# Phase_Modulator_Transmitter.net
KiCad netlist of a schematic drawn in Altium Designer
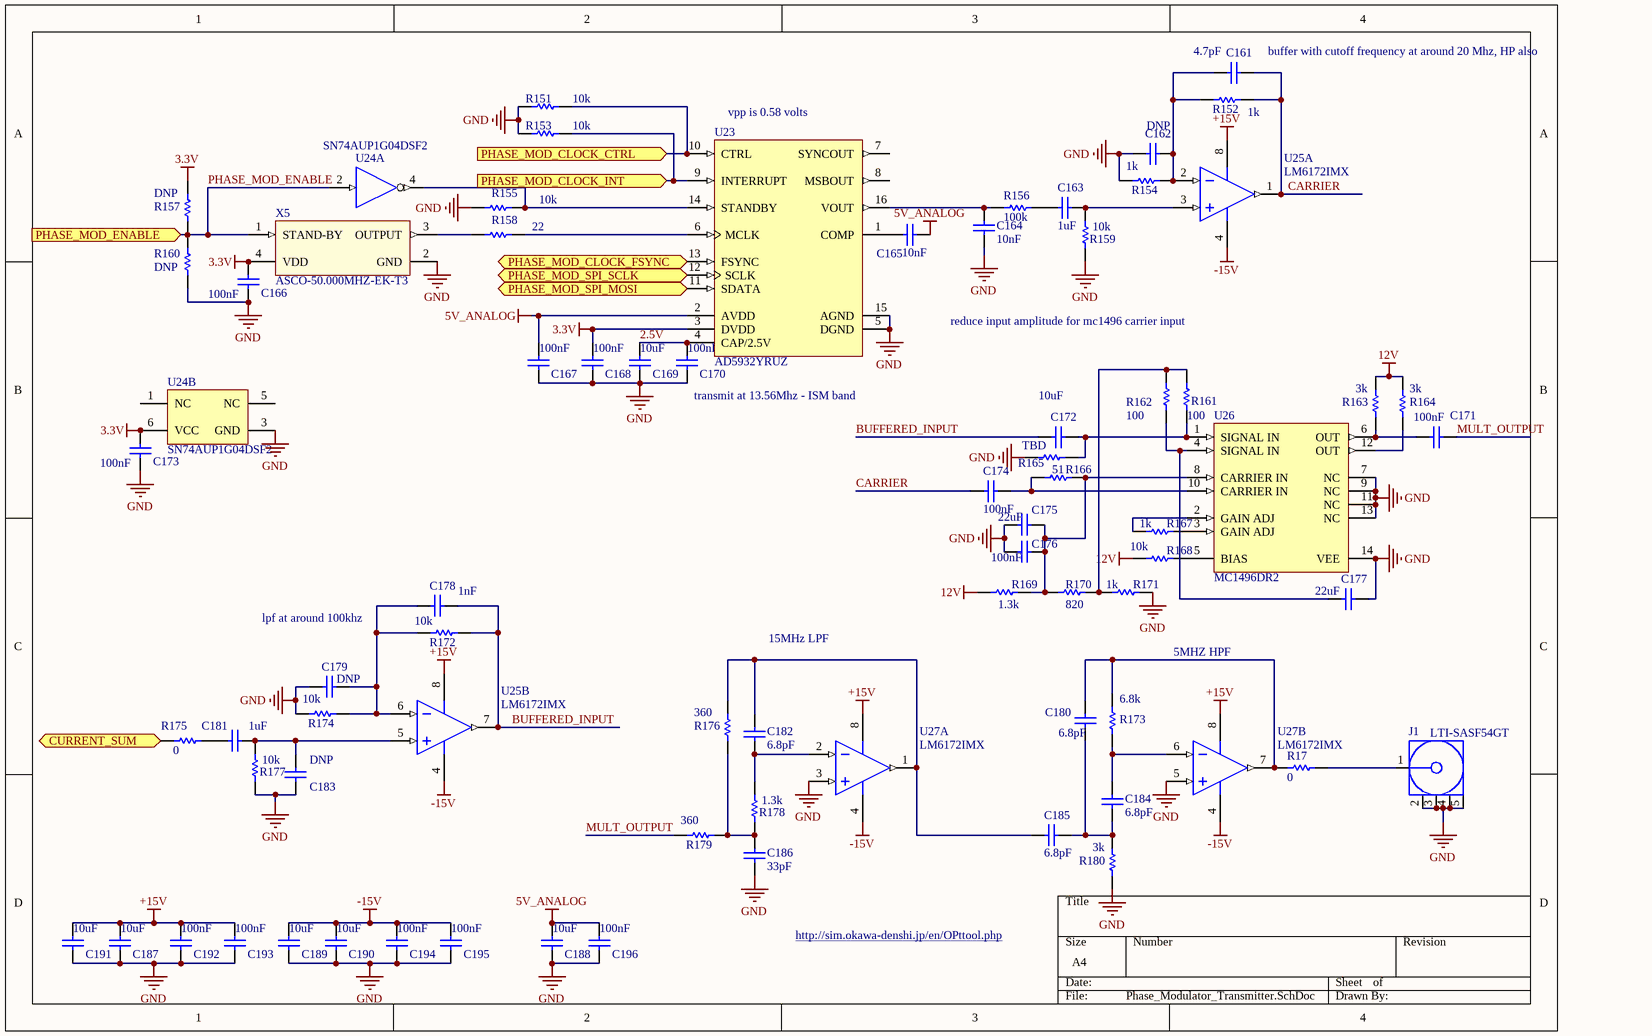
[diagram p0: Phase_Modulator_Transmitter.SchDoc]

(export (version "E")
  (design (tool "Eeschema 10.0.6"))
  (components
    (comp (ref "C161")
      (value "4.7pF")
      (footprint "CAPC0402(1005)60_L")
      (description "0402 (1005 Metric) Chip Capacitor")
      (fields (field (name "Comment") "CAP0402"))
      (libsource (lib "Altium Content Vault") (part "CMP-1590-00004-1"))
    )
    (comp (ref "C162")
      (value "DNP")
      (footprint "CAPC0402(1005)60_L")
      (description "0402 (1005 Metric) Chip Capacitor")
      (fields (field (name "Comment") "CAP0402"))
      (libsource (lib "Altium Content Vault") (part "CMP-1590-00004-1"))
    )
    (comp (ref "C163")
      (value "1uF")
      (footprint "CAPC0402(1005)60_L")
      (description "0402 (1005 Metric) Chip Capacitor")
      (fields (field (name "Comment") "CAP0402"))
      (libsource (lib "Altium Content Vault") (part "CMP-1590-00004-1"))
    )
    (comp (ref "C164")
      (value "10nF")
      (footprint "CAPC0402(1005)60_L")
      (description "0402 (1005 Metric) Chip Capacitor")
      (fields (field (name "Comment") "CAP0402"))
      (libsource (lib "Altium Content Vault") (part "CMP-1590-00004-1"))
    )
    (comp (ref "C165")
      (value "10nF")
      (footprint "CAPC0402(1005)60_L")
      (description "0402 (1005 Metric) Chip Capacitor")
      (fields (field (name "Comment") "CAP0402"))
      (libsource (lib "Altium Content Vault") (part "CMP-1590-00004-1"))
    )
    (comp (ref "C166")
      (value "100nF")
      (footprint "CAPC0402(1005)60_L")
      (description "0402 (1005 Metric) Chip Capacitor")
      (fields (field (name "Comment") "CAP0402"))
      (libsource (lib "Altium Content Vault") (part "CMP-1590-00004-1"))
    )
    (comp (ref "C167")
      (value "100nF")
      (footprint "CAPC0402(1005)60_L")
      (description "0402 (1005 Metric) Chip Capacitor")
      (fields (field (name "Comment") "CAP0402"))
      (libsource (lib "Altium Content Vault") (part "CMP-1590-00004-1"))
    )
    (comp (ref "C168")
      (value "100nF")
      (footprint "CAPC0402(1005)60_L")
      (description "0402 (1005 Metric) Chip Capacitor")
      (fields (field (name "Comment") "CAP0402"))
      (libsource (lib "Altium Content Vault") (part "CMP-1590-00004-1"))
    )
    (comp (ref "C169")
      (value "10uF")
      (footprint "CAPC0402(1005)60_L")
      (description "0402 (1005 Metric) Chip Capacitor")
      (fields (field (name "Comment") "CAP0402"))
      (libsource (lib "Altium Content Vault") (part "CMP-1590-00004-1"))
    )
    (comp (ref "C170")
      (value "100nF")
      (footprint "CAPC0402(1005)60_L")
      (description "0402 (1005 Metric) Chip Capacitor")
      (fields (field (name "Comment") "CAP0402"))
      (libsource (lib "Altium Content Vault") (part "CMP-1590-00004-1"))
    )
    (comp (ref "C171")
      (value "CAP0402")
      (footprint "CAPC0402(1005)60_L")
      (description "0402 (1005 Metric) Chip Capacitor")
      (fields (field (name "TOLERANCE") "100nF"))
      (libsource (lib "Altium Content Vault") (part "CMP-1590-00004-1"))
    )
    (comp (ref "C172")
      (value "10uF")
      (footprint "CAPC0805(2012)145_L")
      (description "0805 (2012 Metric) Chip Capacitor")
      (fields (field (name "Comment") "CAP0805"))
      (libsource (lib "Altium Content Vault") (part "CMP-1590-00003-1"))
    )
    (comp (ref "C173")
      (value "100nF")
      (footprint "CAPC0402(1005)60_L")
      (description "0402 (1005 Metric) Chip Capacitor")
      (fields (field (name "Comment") "CAP0402"))
      (libsource (lib "Altium Content Vault") (part "CMP-1590-00004-1"))
    )
    (comp (ref "C174")
      (value "100nF")
      (footprint "CAPC0402(1005)60_L")
      (description "0402 (1005 Metric) Chip Capacitor")
      (fields (field (name "Comment") "CAP0402"))
      (libsource (lib "Altium Content Vault") (part "CMP-1590-00004-1"))
    )
    (comp (ref "C175")
      (value "22uF")
      (footprint "CAPC0805(2012)145_L")
      (description "0805 (2012 Metric) Chip Capacitor")
      (fields (field (name "Comment") "CAP0805"))
      (libsource (lib "Altium Content Vault") (part "CMP-1590-00003-1"))
    )
    (comp (ref "C176")
      (value "100nF")
      (footprint "CAPC0402(1005)60_L")
      (description "0402 (1005 Metric) Chip Capacitor")
      (fields (field (name "Comment") "CAP0402"))
      (libsource (lib "Altium Content Vault") (part "CMP-1590-00004-1"))
    )
    (comp (ref "C177")
      (value "22uF")
      (footprint "CAPC0805(2012)145_L")
      (description "0805 (2012 Metric) Chip Capacitor")
      (fields (field (name "Comment") "CAP0805"))
      (libsource (lib "Altium Content Vault") (part "CMP-1590-00003-1"))
    )
    (comp (ref "C178")
      (value "1nF")
      (footprint "CAPC0402(1005)60_L")
      (description "0402 (1005 Metric) Chip Capacitor")
      (fields (field (name "Comment") "CAP0402"))
      (libsource (lib "Altium Content Vault") (part "CMP-1590-00004-1"))
    )
    (comp (ref "C179")
      (value "DNP")
      (footprint "CAPC0402(1005)60_L")
      (description "0402 (1005 Metric) Chip Capacitor")
      (fields (field (name "Comment") "CAP0402"))
      (libsource (lib "Altium Content Vault") (part "CMP-1590-00004-1"))
    )
    (comp (ref "C180")
      (value "6.8pF")
      (footprint "CAPC0402(1005)60_L")
      (description "0402 (1005 Metric) Chip Capacitor")
      (fields (field (name "Comment") "CAP0402"))
      (libsource (lib "Altium Content Vault") (part "CMP-1590-00004-1"))
    )
    (comp (ref "C181")
      (value "1uF")
      (footprint "CAPC0402(1005)60_L")
      (description "0402 (1005 Metric) Chip Capacitor")
      (fields (field (name "Comment") "CAP0402"))
      (libsource (lib "Altium Content Vault") (part "CMP-1590-00004-1"))
    )
    (comp (ref "C182")
      (value "6.8pF")
      (footprint "CAPC0402(1005)60_L")
      (description "0402 (1005 Metric) Chip Capacitor")
      (fields (field (name "Comment") "CAP0402"))
      (libsource (lib "Altium Content Vault") (part "CMP-1590-00004-1"))
    )
    (comp (ref "C183")
      (value "DNP")
      (footprint "CAPC0402(1005)60_L")
      (description "0402 (1005 Metric) Chip Capacitor")
      (fields (field (name "Comment") "CAP0402"))
      (libsource (lib "Altium Content Vault") (part "CMP-1590-00004-1"))
    )
    (comp (ref "C184")
      (value "6.8pF")
      (footprint "CAPC0402(1005)60_L")
      (description "0402 (1005 Metric) Chip Capacitor")
      (fields (field (name "Comment") "CAP0402"))
      (libsource (lib "Altium Content Vault") (part "CMP-1590-00004-1"))
    )
    (comp (ref "C185")
      (value "6.8pF")
      (footprint "CAPC0402(1005)60_L")
      (description "0402 (1005 Metric) Chip Capacitor")
      (fields (field (name "Comment") "CAP0402"))
      (libsource (lib "Altium Content Vault") (part "CMP-1590-00004-1"))
    )
    (comp (ref "C186")
      (value "33pF")
      (footprint "CAPC0402(1005)60_L")
      (description "0402 (1005 Metric) Chip Capacitor")
      (fields (field (name "Comment") "CAP0402"))
      (libsource (lib "Altium Content Vault") (part "CMP-1590-00004-1"))
    )
    (comp (ref "C187")
      (value "10uF")
      (footprint "CAPC0805(2012)145_L")
      (description "0805 (2012 Metric) Chip Capacitor")
      (fields (field (name "Comment") "CAP0805"))
      (libsource (lib "Altium Content Vault") (part "CMP-1590-00003-1"))
    )
    (comp (ref "C188")
      (value "10uF")
      (footprint "CAPC0805(2012)145_L")
      (description "0805 (2012 Metric) Chip Capacitor")
      (fields (field (name "Comment") "CAP0805"))
      (libsource (lib "Altium Content Vault") (part "CMP-1590-00003-1"))
    )
    (comp (ref "C189")
      (value "10uF")
      (footprint "CAPC0805(2012)145_L")
      (description "0805 (2012 Metric) Chip Capacitor")
      (fields (field (name "Comment") "CAP0805"))
      (libsource (lib "Altium Content Vault") (part "CMP-1590-00003-1"))
    )
    (comp (ref "C190")
      (value "10uF")
      (footprint "CAPC0805(2012)145_L")
      (description "0805 (2012 Metric) Chip Capacitor")
      (fields (field (name "Comment") "CAP0805"))
      (libsource (lib "Altium Content Vault") (part "CMP-1590-00003-1"))
    )
    (comp (ref "C191")
      (value "10uF")
      (footprint "CAPC0805(2012)145_L")
      (description "0805 (2012 Metric) Chip Capacitor")
      (fields (field (name "Comment") "CAP0805"))
      (libsource (lib "Altium Content Vault") (part "CMP-1590-00003-1"))
    )
    (comp (ref "C192")
      (value "100nF")
      (footprint "CAPC0402(1005)60_L")
      (description "0402 (1005 Metric) Chip Capacitor")
      (fields (field (name "Comment") "CAP0402"))
      (libsource (lib "Altium Content Vault") (part "CMP-1590-00004-1"))
    )
    (comp (ref "C193")
      (value "100nF")
      (footprint "CAPC0402(1005)60_L")
      (description "0402 (1005 Metric) Chip Capacitor")
      (fields (field (name "Comment") "CAP0402"))
      (libsource (lib "Altium Content Vault") (part "CMP-1590-00004-1"))
    )
    (comp (ref "C194")
      (value "100nF")
      (footprint "CAPC0402(1005)60_L")
      (description "0402 (1005 Metric) Chip Capacitor")
      (fields (field (name "Comment") "CAP0402"))
      (libsource (lib "Altium Content Vault") (part "CMP-1590-00004-1"))
    )
    (comp (ref "C195")
      (value "100nF")
      (footprint "CAPC0402(1005)60_L")
      (description "0402 (1005 Metric) Chip Capacitor")
      (fields (field (name "Comment") "CAP0402"))
      (libsource (lib "Altium Content Vault") (part "CMP-1590-00004-1"))
    )
    (comp (ref "C196")
      (value "100nF")
      (footprint "CAPC0402(1005)60_L")
      (description "0402 (1005 Metric) Chip Capacitor")
      (fields (field (name "Comment") "CAP0402"))
      (libsource (lib "Altium Content Vault") (part "CMP-1590-00004-1"))
    )
    (comp (ref "J1")
      (value "LTI-SASF54GT")
      (footprint "LHT-LTI-SASF54GT_V")
      (description "SMA Connector, Pitch 2.54 mm, 1 Position, Height 9.5 mm, Tail Length 4 mm, RoHS")
      (fields (field (name "MANUFACTURER") "Lighthorse Technologies Inc."))
      (libsource (lib "Altium Content Vault") (part "CN-S-F-RF5"))
    )
    (comp (ref "R17")
      (value "0")
      (footprint "RESC0402(1005)_L")
      (description "0402 (1005 Metric) Chip Resistor")
      (fields (field (name "Comment") "RES0402"))
      (libsource (lib "Altium Content Vault") (part "CMP-1591-00004-1"))
    )
    (comp (ref "R151")
      (value "10k")
      (footprint "RESC0402(1005)_L")
      (description "0402 (1005 Metric) Chip Resistor")
      (fields (field (name "Comment") "RES0402"))
      (libsource (lib "Altium Content Vault") (part "CMP-1591-00004-1"))
    )
    (comp (ref "R152")
      (value "1k")
      (footprint "RESC0402(1005)_L")
      (description "0402 (1005 Metric) Chip Resistor")
      (fields (field (name "Comment") "RES0402"))
      (libsource (lib "Altium Content Vault") (part "CMP-1591-00004-1"))
    )
    (comp (ref "R153")
      (value "10k")
      (footprint "RESC0402(1005)_L")
      (description "0402 (1005 Metric) Chip Resistor")
      (fields (field (name "Comment") "RES0402"))
      (libsource (lib "Altium Content Vault") (part "CMP-1591-00004-1"))
    )
    (comp (ref "R154")
      (value "1k")
      (footprint "RESC0402(1005)_L")
      (description "0402 (1005 Metric) Chip Resistor")
      (fields (field (name "Comment") "RES0402"))
      (libsource (lib "Altium Content Vault") (part "CMP-1591-00004-1"))
    )
    (comp (ref "R155")
      (value "10k")
      (footprint "RESC0402(1005)_L")
      (description "0402 (1005 Metric) Chip Resistor")
      (fields (field (name "Comment") "RES0402"))
      (libsource (lib "Altium Content Vault") (part "CMP-1591-00004-1"))
    )
    (comp (ref "R156")
      (value "100k")
      (footprint "RESC0402(1005)_L")
      (description "0402 (1005 Metric) Chip Resistor")
      (fields (field (name "Comment") "RES0402"))
      (libsource (lib "Altium Content Vault") (part "CMP-1591-00004-1"))
    )
    (comp (ref "R157")
      (value "DNP")
      (footprint "RESC0402(1005)_L")
      (description "0402 (1005 Metric) Chip Resistor")
      (fields (field (name "Comment") "RES0402"))
      (libsource (lib "Altium Content Vault") (part "CMP-1591-00004-1"))
    )
    (comp (ref "R158")
      (value "22")
      (footprint "RESC0402(1005)_L")
      (description "0402 (1005 Metric) Chip Resistor")
      (fields (field (name "Comment") "RES0402"))
      (libsource (lib "Altium Content Vault") (part "CMP-1591-00004-1"))
    )
    (comp (ref "R159")
      (value "10k")
      (footprint "RESC0402(1005)_L")
      (description "0402 (1005 Metric) Chip Resistor")
      (fields (field (name "Comment") "RES0402"))
      (libsource (lib "Altium Content Vault") (part "CMP-1591-00004-1"))
    )
    (comp (ref "R160")
      (value "DNP")
      (footprint "RESC0402(1005)_L")
      (description "0402 (1005 Metric) Chip Resistor")
      (fields (field (name "Comment") "RES0402"))
      (libsource (lib "Altium Content Vault") (part "CMP-1591-00004-1"))
    )
    (comp (ref "R161")
      (value "100")
      (footprint "RESC0402(1005)_L")
      (description "0402 (1005 Metric) Chip Resistor")
      (fields (field (name "Comment") "RES0402"))
      (libsource (lib "Altium Content Vault") (part "CMP-1591-00004-1"))
    )
    (comp (ref "R162")
      (value "100")
      (footprint "RESC0402(1005)_L")
      (description "0402 (1005 Metric) Chip Resistor")
      (fields (field (name "Comment") "RES0402"))
      (libsource (lib "Altium Content Vault") (part "CMP-1591-00004-1"))
    )
    (comp (ref "R163")
      (value "3k")
      (footprint "RESC0402(1005)_L")
      (description "0402 (1005 Metric) Chip Resistor")
      (fields (field (name "Comment") "RES0402"))
      (libsource (lib "Altium Content Vault") (part "CMP-1591-00004-1"))
    )
    (comp (ref "R164")
      (value "3k")
      (footprint "RESC0402(1005)_L")
      (description "0402 (1005 Metric) Chip Resistor")
      (fields (field (name "Comment") "RES0402"))
      (libsource (lib "Altium Content Vault") (part "CMP-1591-00004-1"))
    )
    (comp (ref "R165")
      (value "TBD")
      (footprint "RESC0402(1005)_L")
      (description "0402 (1005 Metric) Chip Resistor")
      (fields (field (name "Comment") "RES0402"))
      (libsource (lib "Altium Content Vault") (part "CMP-1591-00004-1"))
    )
    (comp (ref "R166")
      (value "51")
      (footprint "RESC0402(1005)_L")
      (description "0402 (1005 Metric) Chip Resistor")
      (fields (field (name "Comment") "RES0402"))
      (libsource (lib "Altium Content Vault") (part "CMP-1591-00004-1"))
    )
    (comp (ref "R167")
      (value "1k")
      (footprint "RESC0402(1005)_L")
      (description "0402 (1005 Metric) Chip Resistor")
      (fields (field (name "Comment") "RES0402"))
      (libsource (lib "Altium Content Vault") (part "CMP-1591-00004-1"))
    )
    (comp (ref "R168")
      (value "10k")
      (footprint "RESC0402(1005)_L")
      (description "0402 (1005 Metric) Chip Resistor")
      (fields (field (name "Comment") "RES0402"))
      (libsource (lib "Altium Content Vault") (part "CMP-1591-00004-1"))
    )
    (comp (ref "R169")
      (value "1.3k")
      (footprint "RESC0402(1005)_L")
      (description "0402 (1005 Metric) Chip Resistor")
      (fields (field (name "Comment") "RES0402"))
      (libsource (lib "Altium Content Vault") (part "CMP-1591-00004-1"))
    )
    (comp (ref "R170")
      (value "820")
      (footprint "RESC0402(1005)_L")
      (description "0402 (1005 Metric) Chip Resistor")
      (fields (field (name "Comment") "RES0402"))
      (libsource (lib "Altium Content Vault") (part "CMP-1591-00004-1"))
    )
    (comp (ref "R171")
      (value "1k")
      (footprint "RESC0402(1005)_L")
      (description "0402 (1005 Metric) Chip Resistor")
      (fields (field (name "Comment") "RES0402"))
      (libsource (lib "Altium Content Vault") (part "CMP-1591-00004-1"))
    )
    (comp (ref "R172")
      (value "10k")
      (footprint "RESC0402(1005)_L")
      (description "0402 (1005 Metric) Chip Resistor")
      (fields (field (name "Comment") "RES0402"))
      (libsource (lib "Altium Content Vault") (part "CMP-1591-00004-1"))
    )
    (comp (ref "R173")
      (value "6.8k")
      (footprint "RESC0402(1005)_L")
      (description "0402 (1005 Metric) Chip Resistor")
      (fields (field (name "Comment") "RES0402"))
      (libsource (lib "Altium Content Vault") (part "CMP-1591-00004-1"))
    )
    (comp (ref "R174")
      (value "10k")
      (footprint "RESC0402(1005)_L")
      (description "0402 (1005 Metric) Chip Resistor")
      (fields (field (name "Comment") "RES0402"))
      (libsource (lib "Altium Content Vault") (part "CMP-1591-00004-1"))
    )
    (comp (ref "R175")
      (value "0")
      (footprint "RESC0402(1005)_L")
      (description "0402 (1005 Metric) Chip Resistor")
      (fields (field (name "Comment") "RES0402"))
      (libsource (lib "Altium Content Vault") (part "CMP-1591-00004-1"))
    )
    (comp (ref "R176")
      (value "360")
      (footprint "RESC0402(1005)_L")
      (description "0402 (1005 Metric) Chip Resistor")
      (fields (field (name "Comment") "RES0402"))
      (libsource (lib "Altium Content Vault") (part "CMP-1591-00004-1"))
    )
    (comp (ref "R177")
      (value "10k")
      (footprint "RESC0402(1005)_L")
      (description "0402 (1005 Metric) Chip Resistor")
      (fields (field (name "Comment") "RES0402"))
      (libsource (lib "Altium Content Vault") (part "CMP-1591-00004-1"))
    )
    (comp (ref "R178")
      (value "1.3k")
      (footprint "RESC0402(1005)_L")
      (description "0402 (1005 Metric) Chip Resistor")
      (fields (field (name "Comment") "RES0402"))
      (libsource (lib "Altium Content Vault") (part "CMP-1591-00004-1"))
    )
    (comp (ref "R179")
      (value "360")
      (footprint "RESC0402(1005)_L")
      (description "0402 (1005 Metric) Chip Resistor")
      (fields (field (name "Comment") "RES0402"))
      (libsource (lib "Altium Content Vault") (part "CMP-1591-00004-1"))
    )
    (comp (ref "R180")
      (value "3k")
      (footprint "RESC0402(1005)_L")
      (description "0402 (1005 Metric) Chip Resistor")
      (fields (field (name "Comment") "RES0402"))
      (libsource (lib "Altium Content Vault") (part "CMP-1591-00004-1"))
    )
    (comp (ref "U23")
      (value "AD5932YRUZ")
      (footprint "ADI-RU-16_M")
      (description "Programmable Frequency Scan Waveform Generator, 10-Bit, Serial, RU-16, 96 Tube, Pb-Free")
      (libsource (lib "Altium Content Vault") (part "ADI-AD5932-RU-16"))
    )
    (comp (ref "U24")
      (value "SN74AUP1G04DSF2")
      (footprint "DSF0006A_V")
      (description "Low-Power Single Inverter Gate, DSF0006A, LARGE T&R")
      (fields
        (field (name "MANUFACTURER") "Texas Instruments")
        (field (name "GENERIC PART NUMBER") "SN74AUP1G04")
      )
      (libsource (lib "Altium Content Vault") (part "TI-SN74XXX1GX4-6"))
    )
    (comp (ref "U25")
      (value "LM6172IMX")
      (footprint "D0008A_L")
      (description "Dual High Speed, Low Power, Low Distortion Voltage Feedback Amplifiers, 8-pin Narrow SOIC")
      (fields (field (name "MANUFACTURER") "Texas Instruments"))
      (libsource (lib "Altium Content Vault") (part "AMP-OPA-LM6132-8"))
    )
    (comp (ref "U26")
      (value "MC1496DR2")
      (footprint "ONSC-SOIC-14-751A-03_H_V")
      (description "Balanced Modulator / Demodulator, 0 to 70 degC, 14-Pin SOIC, Tape and Reel")
      (fields (field (name "MANUFACTURER") "On Semiconductor"))
      (libsource (lib "Altium Content Vault") (part "ONSC-MC1496_B-14"))
    )
    (comp (ref "U27")
      (value "LM6172IMX")
      (footprint "D0008A_L")
      (description "Dual High Speed, Low Power, Low Distortion Voltage Feedback Amplifiers, 8-pin Narrow SOIC")
      (fields (field (name "MANUFACTURER") "Texas Instruments"))
      (libsource (lib "Altium Content Vault") (part "AMP-OPA-LM6132-8"))
    )
    (comp (ref "X5")
      (value "ASCO-50.000MHZ-EK-T3")
      (footprint "ABRA-ASCO-50.000MHZ-EK-T3-4_V")
      (description "Crystal Clock Oscillator, 50 MHz, -20 to 70 degC, 1.6 x 1.2 x 0.7 mm SMD")
      (fields (field (name "MANUFACTURER") "Abracon"))
      (libsource (lib "Altium Content Vault") (part "ABRA-ASCO-50_000MHZ-EK-T3-4"))
    )
  )
  (nets
    (net (code "1") (name "+15V") (class "Default")
      (node (ref "C187") (pin "2") (pinfunction "2_2") (pintype "passive"))
      (node (ref "C191") (pin "2") (pinfunction "2_2") (pintype "passive"))
      (node (ref "C192") (pin "1") (pinfunction "1_1") (pintype "passive"))
      (node (ref "C193") (pin "1") (pinfunction "1_1") (pintype "passive"))
      (node (ref "U25") (pin "8") (pinfunction "V+_8") (pintype "power_in"))
      (node (ref "U27") (pin "8") (pinfunction "V+_8") (pintype "power_in"))
    )
    (net (code "2") (name "-15V") (class "Default")
      (node (ref "C189") (pin "2") (pinfunction "2_2") (pintype "passive"))
      (node (ref "C190") (pin "2") (pinfunction "2_2") (pintype "passive"))
      (node (ref "C194") (pin "1") (pinfunction "1_1") (pintype "passive"))
      (node (ref "C195") (pin "1") (pinfunction "1_1") (pintype "passive"))
      (node (ref "U25") (pin "4") (pinfunction "V-_4") (pintype "power_in"))
      (node (ref "U27") (pin "4") (pinfunction "V-_4") (pintype "power_in"))
    )
    (net (code "3") (name "/2.5V") (class "Default")
      (node (ref "C169") (pin "1") (pinfunction "1_1") (pintype "passive"))
      (node (ref "C170") (pin "1") (pinfunction "1_1") (pintype "passive"))
      (node (ref "U23") (pin "4") (pinfunction "CAP/2.5V_4") (pintype "power_in"))
    )
    (net (code "4") (name "/BUFFERED_INPUT") (class "Default")
      (node (ref "C172") (pin "1") (pinfunction "1_1") (pintype "passive"))
      (node (ref "C178") (pin "2") (pinfunction "2_2") (pintype "passive"))
      (node (ref "R172") (pin "2") (pinfunction "2_2") (pintype "passive"))
      (node (ref "U25") (pin "7") (pinfunction "OUTB_7") (pintype "output"))
    )
    (net (code "5") (name "/CARRIER") (class "Default")
      (node (ref "C161") (pin "2") (pinfunction "2_2") (pintype "passive"))
      (node (ref "C174") (pin "1") (pinfunction "1_1") (pintype "passive"))
      (node (ref "R152") (pin "2") (pinfunction "2_2") (pintype "passive"))
      (node (ref "U25") (pin "1") (pinfunction "OUTA_1") (pintype "output"))
    )
    (net (code "6") (name "/CURRENT_SUM") (class "Default")
      (node (ref "R175") (pin "1") (pinfunction "1_1") (pintype "passive"))
    )
    (net (code "7") (name "/MULT_OUTPUT") (class "Default")
      (node (ref "C171") (pin "2") (pinfunction "2_2") (pintype "passive"))
      (node (ref "R179") (pin "1") (pinfunction "1_1") (pintype "passive"))
    )
    (net (code "8") (name "/PHASE_MOD_CLOCK_CTRL") (class "Default")
      (node (ref "R151") (pin "1") (pinfunction "1_1") (pintype "passive"))
      (node (ref "U23") (pin "10") (pinfunction "CTRL_10") (pintype "input"))
    )
    (net (code "9") (name "/PHASE_MOD_CLOCK_FSYNC") (class "Default")
      (node (ref "U23") (pin "13") (pinfunction "FSYNC_13") (pintype "input"))
    )
    (net (code "10") (name "/PHASE_MOD_CLOCK_INT") (class "Default")
      (node (ref "R153") (pin "1") (pinfunction "1_1") (pintype "passive"))
      (node (ref "U23") (pin "9") (pinfunction "INTERRUPT_9") (pintype "input"))
    )
    (net (code "11") (name "/PHASE_MOD_ENABLE") (class "Default")
      (node (ref "R157") (pin "1") (pinfunction "1_1") (pintype "passive"))
      (node (ref "R160") (pin "2") (pinfunction "2_2") (pintype "passive"))
      (node (ref "U24") (pin "2") (pinfunction "A_2") (pintype "input"))
      (node (ref "X5") (pin "1") (pinfunction "STAND-BY_1") (pintype "input"))
    )
    (net (code "12") (name "/PHASE_MOD_SPI_MOSI") (class "Default")
      (node (ref "U23") (pin "11") (pinfunction "SDATA_11") (pintype "input"))
    )
    (net (code "13") (name "/PHASE_MOD_SPI_SCLK") (class "Default")
      (node (ref "U23") (pin "12") (pinfunction "SCLK_12") (pintype "input"))
    )
    (net (code "14") (name "3.3V") (class "Default")
      (node (ref "C166") (pin "1") (pinfunction "1_1") (pintype "passive"))
      (node (ref "C168") (pin "1") (pinfunction "1_1") (pintype "passive"))
      (node (ref "C173") (pin "1") (pinfunction "1_1") (pintype "passive"))
      (node (ref "R157") (pin "2") (pinfunction "2_2") (pintype "passive"))
      (node (ref "U23") (pin "3") (pinfunction "DVDD_3") (pintype "power_in"))
      (node (ref "U24") (pin "6") (pinfunction "VCC_6") (pintype "power_in"))
      (node (ref "X5") (pin "4") (pinfunction "VDD_4") (pintype "power_in"))
    )
    (net (code "15") (name "5V_ANALOG") (class "Default")
      (node (ref "C165") (pin "2") (pinfunction "2_2") (pintype "passive"))
      (node (ref "C167") (pin "1") (pinfunction "1_1") (pintype "passive"))
      (node (ref "C188") (pin "2") (pinfunction "2_2") (pintype "passive"))
      (node (ref "C196") (pin "1") (pinfunction "1_1") (pintype "passive"))
      (node (ref "U23") (pin "2") (pinfunction "AVDD_2") (pintype "power_in"))
    )
    (net (code "16") (name "12V") (class "Default")
      (node (ref "R163") (pin "1") (pinfunction "1_1") (pintype "passive"))
      (node (ref "R164") (pin "1") (pinfunction "1_1") (pintype "passive"))
      (node (ref "R168") (pin "2") (pinfunction "2_2") (pintype "passive"))
      (node (ref "R169") (pin "2") (pinfunction "2_2") (pintype "passive"))
    )
    (net (code "17") (name "GND") (class "Default")
      (node (ref "C162") (pin "1") (pinfunction "1_1") (pintype "passive"))
      (node (ref "C164") (pin "1") (pinfunction "1_1") (pintype "passive"))
      (node (ref "C166") (pin "2") (pinfunction "2_2") (pintype "passive"))
      (node (ref "C167") (pin "2") (pinfunction "2_2") (pintype "passive"))
      (node (ref "C168") (pin "2") (pinfunction "2_2") (pintype "passive"))
      (node (ref "C169") (pin "2") (pinfunction "2_2") (pintype "passive"))
      (node (ref "C170") (pin "2") (pinfunction "2_2") (pintype "passive"))
      (node (ref "C173") (pin "2") (pinfunction "2_2") (pintype "passive"))
      (node (ref "C175") (pin "1") (pinfunction "1_1") (pintype "passive"))
      (node (ref "C176") (pin "1") (pinfunction "1_1") (pintype "passive"))
      (node (ref "C177") (pin "2") (pinfunction "2_2") (pintype "passive"))
      (node (ref "C179") (pin "1") (pinfunction "1_1") (pintype "passive"))
      (node (ref "C183") (pin "2") (pinfunction "2_2") (pintype "passive"))
      (node (ref "C186") (pin "2") (pinfunction "2_2") (pintype "passive"))
      (node (ref "C187") (pin "1") (pinfunction "1_1") (pintype "passive"))
      (node (ref "C188") (pin "1") (pinfunction "1_1") (pintype "passive"))
      (node (ref "C189") (pin "1") (pinfunction "1_1") (pintype "passive"))
      (node (ref "C190") (pin "1") (pinfunction "1_1") (pintype "passive"))
      (node (ref "C191") (pin "1") (pinfunction "1_1") (pintype "passive"))
      (node (ref "C192") (pin "2") (pinfunction "2_2") (pintype "passive"))
      (node (ref "C193") (pin "2") (pinfunction "2_2") (pintype "passive"))
      (node (ref "C194") (pin "2") (pinfunction "2_2") (pintype "passive"))
      (node (ref "C195") (pin "2") (pinfunction "2_2") (pintype "passive"))
      (node (ref "C196") (pin "2") (pinfunction "2_2") (pintype "passive"))
      (node (ref "J1") (pin "2") (pinfunction "2_2") (pintype "passive"))
      (node (ref "J1") (pin "3") (pinfunction "3_3") (pintype "passive"))
      (node (ref "J1") (pin "4") (pinfunction "4_4") (pintype "passive"))
      (node (ref "J1") (pin "5") (pinfunction "5_5") (pintype "passive"))
      (node (ref "R151") (pin "2") (pinfunction "2_2") (pintype "passive"))
      (node (ref "R153") (pin "2") (pinfunction "2_2") (pintype "passive"))
      (node (ref "R154") (pin "1") (pinfunction "1_1") (pintype "passive"))
      (node (ref "R155") (pin "2") (pinfunction "2_2") (pintype "passive"))
      (node (ref "R159") (pin "1") (pinfunction "1_1") (pintype "passive"))
      (node (ref "R160") (pin "1") (pinfunction "1_1") (pintype "passive"))
      (node (ref "R165") (pin "1") (pinfunction "1_1") (pintype "passive"))
      (node (ref "R171") (pin "1") (pinfunction "1_1") (pintype "passive"))
      (node (ref "R174") (pin "1") (pinfunction "1_1") (pintype "passive"))
      (node (ref "R177") (pin "2") (pinfunction "2_2") (pintype "passive"))
      (node (ref "R180") (pin "2") (pinfunction "2_2") (pintype "passive"))
      (node (ref "U23") (pin "15") (pinfunction "AGND_15") (pintype "power_in"))
      (node (ref "U23") (pin "5") (pinfunction "DGND_5") (pintype "power_in"))
      (node (ref "U24") (pin "3") (pinfunction "GND_3") (pintype "power_in"))
      (node (ref "U26") (pin "11") (pinfunction "NC_11") (pintype "passive"))
      (node (ref "U26") (pin "13") (pinfunction "NC_13") (pintype "passive"))
      (node (ref "U26") (pin "14") (pinfunction "VEE_14") (pintype "power_in"))
      (node (ref "U26") (pin "7") (pinfunction "NC_7") (pintype "passive"))
      (node (ref "U26") (pin "9") (pinfunction "NC_9") (pintype "passive"))
      (node (ref "U27") (pin "3") (pinfunction "INA+_3") (pintype "input"))
      (node (ref "U27") (pin "5") (pinfunction "INB+_5") (pintype "input"))
      (node (ref "X5") (pin "2") (pinfunction "GND_2") (pintype "power_in"))
    )
    (net (code "18") (name "Net-(C163-Pad2)") (class "Default")
      (node (ref "C163") (pin "2") (pinfunction "2_2") (pintype "passive"))
      (node (ref "R156") (pin "1") (pinfunction "1_1") (pintype "passive"))
    )
    (net (code "19") (name "Net-(C171-Pad1)") (class "Default")
      (node (ref "C171") (pin "1") (pinfunction "1_1") (pintype "passive"))
      (node (ref "R163") (pin "2") (pinfunction "2_2") (pintype "passive"))
      (node (ref "U26") (pin "6") (pinfunction "OUT_6") (pintype "output"))
    )
    (net (code "20") (name "Net-(C172-Pad2)") (class "Default")
      (node (ref "C172") (pin "2") (pinfunction "2_2") (pintype "passive"))
      (node (ref "R161") (pin "2") (pinfunction "2_2") (pintype "passive"))
      (node (ref "R165") (pin "2") (pinfunction "2_2") (pintype "passive"))
      (node (ref "U26") (pin "1") (pinfunction "SIGNAL_IN_1") (pintype "input"))
    )
    (net (code "21") (name "Net-(C174-Pad2)") (class "Default")
      (node (ref "C174") (pin "2") (pinfunction "2_2") (pintype "passive"))
      (node (ref "R166") (pin "2") (pinfunction "2_2") (pintype "passive"))
      (node (ref "U26") (pin "10") (pinfunction "CARRIER_IN_10") (pintype "input"))
    )
    (net (code "22") (name "Net-(C175-Pad2)") (class "Default")
      (node (ref "C175") (pin "2") (pinfunction "2_2") (pintype "passive"))
      (node (ref "C176") (pin "2") (pinfunction "2_2") (pintype "passive"))
      (node (ref "R166") (pin "1") (pinfunction "1_1") (pintype "passive"))
      (node (ref "R169") (pin "1") (pinfunction "1_1") (pintype "passive"))
      (node (ref "R170") (pin "2") (pinfunction "2_2") (pintype "passive"))
      (node (ref "U26") (pin "8") (pinfunction "CARRIER_IN_8") (pintype "input"))
    )
    (net (code "23") (name "Net-(C177-Pad1)") (class "Default")
      (node (ref "C177") (pin "1") (pinfunction "1_1") (pintype "passive"))
      (node (ref "R162") (pin "2") (pinfunction "2_2") (pintype "passive"))
      (node (ref "U26") (pin "4") (pinfunction "SIGNAL_IN_4") (pintype "input"))
    )
    (net (code "24") (name "Net-(C180-Pad1)") (class "Default")
      (node (ref "C180") (pin "1") (pinfunction "1_1") (pintype "passive"))
      (node (ref "C184") (pin "1") (pinfunction "1_1") (pintype "passive"))
      (node (ref "C185") (pin "1") (pinfunction "1_1") (pintype "passive"))
      (node (ref "R180") (pin "1") (pinfunction "1_1") (pintype "passive"))
    )
    (net (code "25") (name "Net-(C181-Pad1)") (class "Default")
      (node (ref "C181") (pin "1") (pinfunction "1_1") (pintype "passive"))
      (node (ref "R175") (pin "2") (pinfunction "2_2") (pintype "passive"))
    )
    (net (code "26") (name "Net-(C186-Pad1)") (class "Default")
      (node (ref "C186") (pin "1") (pinfunction "1_1") (pintype "passive"))
      (node (ref "R176") (pin "1") (pinfunction "1_1") (pintype "passive"))
      (node (ref "R178") (pin "1") (pinfunction "1_1") (pintype "passive"))
      (node (ref "R179") (pin "2") (pinfunction "2_2") (pintype "passive"))
    )
    (net (code "27") (name "Net-(J1-Pad1)") (class "Default")
      (node (ref "J1") (pin "1") (pinfunction "1_1") (pintype "passive"))
      (node (ref "R17") (pin "2") (pinfunction "2_2") (pintype "passive"))
    )
    (net (code "28") (name "Net-(R161-Pad1)") (class "Default")
      (node (ref "R161") (pin "1") (pinfunction "1_1") (pintype "passive"))
      (node (ref "R162") (pin "1") (pinfunction "1_1") (pintype "passive"))
      (node (ref "R170") (pin "1") (pinfunction "1_1") (pintype "passive"))
      (node (ref "R171") (pin "2") (pinfunction "2_2") (pintype "passive"))
    )
    (net (code "29") (name "Net-(R164-Pad2)") (class "Default")
      (node (ref "R164") (pin "2") (pinfunction "2_2") (pintype "passive"))
      (node (ref "U26") (pin "12") (pinfunction "OUT_12") (pintype "output"))
    )
    (net (code "30") (name "Net-(R167-Pad1)") (class "Default")
      (node (ref "R167") (pin "1") (pinfunction "1_1") (pintype "passive"))
      (node (ref "U26") (pin "3") (pinfunction "GAIN_ADJ_3") (pintype "input"))
    )
    (net (code "31") (name "Net-(R167-Pad2)") (class "Default")
      (node (ref "R167") (pin "2") (pinfunction "2_2") (pintype "passive"))
      (node (ref "U26") (pin "2") (pinfunction "GAIN_ADJ_2") (pintype "input"))
    )
    (net (code "32") (name "Net-(U23-COMP)") (class "Default")
      (node (ref "C165") (pin "1") (pinfunction "1_1") (pintype "passive"))
      (node (ref "U23") (pin "1") (pinfunction "COMP_1") (pintype "passive"))
    )
    (net (code "33") (name "Net-(U23-MCLK)") (class "Default")
      (node (ref "R158") (pin "1") (pinfunction "1_1") (pintype "passive"))
      (node (ref "U23") (pin "6") (pinfunction "MCLK_6") (pintype "input"))
    )
    (net (code "34") (name "Net-(U23-STANDBY)") (class "Default")
      (node (ref "R155") (pin "1") (pinfunction "1_1") (pintype "passive"))
      (node (ref "U23") (pin "14") (pinfunction "STANDBY_14") (pintype "input"))
      (node (ref "U24") (pin "4") (pinfunction "Y_4") (pintype "output"))
    )
    (net (code "35") (name "Net-(U23-VOUT)") (class "Default")
      (node (ref "C164") (pin "2") (pinfunction "2_2") (pintype "passive"))
      (node (ref "R156") (pin "2") (pinfunction "2_2") (pintype "passive"))
      (node (ref "U23") (pin "16") (pinfunction "VOUT_16") (pintype "output"))
    )
    (net (code "36") (name "Net-(U25A-INA+)") (class "Default")
      (node (ref "C163") (pin "1") (pinfunction "1_1") (pintype "passive"))
      (node (ref "R159") (pin "2") (pinfunction "2_2") (pintype "passive"))
      (node (ref "U25") (pin "3") (pinfunction "INA+_3") (pintype "input"))
    )
    (net (code "37") (name "Net-(U25A-INA-)") (class "Default")
      (node (ref "C161") (pin "1") (pinfunction "1_1") (pintype "passive"))
      (node (ref "C162") (pin "2") (pinfunction "2_2") (pintype "passive"))
      (node (ref "R152") (pin "1") (pinfunction "1_1") (pintype "passive"))
      (node (ref "R154") (pin "2") (pinfunction "2_2") (pintype "passive"))
      (node (ref "U25") (pin "2") (pinfunction "INA-_2") (pintype "input"))
    )
    (net (code "38") (name "Net-(U25B-INB+)") (class "Default")
      (node (ref "C181") (pin "2") (pinfunction "2_2") (pintype "passive"))
      (node (ref "C183") (pin "1") (pinfunction "1_1") (pintype "passive"))
      (node (ref "R177") (pin "1") (pinfunction "1_1") (pintype "passive"))
      (node (ref "U25") (pin "5") (pinfunction "INB+_5") (pintype "input"))
    )
    (net (code "39") (name "Net-(U25B-INB-)") (class "Default")
      (node (ref "C178") (pin "1") (pinfunction "1_1") (pintype "passive"))
      (node (ref "C179") (pin "2") (pinfunction "2_2") (pintype "passive"))
      (node (ref "R172") (pin "1") (pinfunction "1_1") (pintype "passive"))
      (node (ref "R174") (pin "2") (pinfunction "2_2") (pintype "passive"))
      (node (ref "U25") (pin "6") (pinfunction "INB-_6") (pintype "input"))
    )
    (net (code "40") (name "Net-(U26-BIAS)") (class "Default")
      (node (ref "R168") (pin "1") (pinfunction "1_1") (pintype "passive"))
      (node (ref "U26") (pin "5") (pinfunction "BIAS_5") (pintype "passive"))
    )
    (net (code "41") (name "Net-(U27A-INA-)") (class "Default")
      (node (ref "C182") (pin "1") (pinfunction "1_1") (pintype "passive"))
      (node (ref "R178") (pin "2") (pinfunction "2_2") (pintype "passive"))
      (node (ref "U27") (pin "2") (pinfunction "INA-_2") (pintype "input"))
    )
    (net (code "42") (name "Net-(U27A-OUTA)") (class "Default")
      (node (ref "C182") (pin "2") (pinfunction "2_2") (pintype "passive"))
      (node (ref "C185") (pin "2") (pinfunction "2_2") (pintype "passive"))
      (node (ref "R176") (pin "2") (pinfunction "2_2") (pintype "passive"))
      (node (ref "U27") (pin "1") (pinfunction "OUTA_1") (pintype "output"))
    )
    (net (code "43") (name "Net-(U27B-INB-)") (class "Default")
      (node (ref "C184") (pin "2") (pinfunction "2_2") (pintype "passive"))
      (node (ref "R173") (pin "2") (pinfunction "2_2") (pintype "passive"))
      (node (ref "U27") (pin "6") (pinfunction "INB-_6") (pintype "input"))
    )
    (net (code "44") (name "Net-(U27B-OUTB)") (class "Default")
      (node (ref "C180") (pin "2") (pinfunction "2_2") (pintype "passive"))
      (node (ref "R17") (pin "1") (pinfunction "1_1") (pintype "passive"))
      (node (ref "R173") (pin "1") (pinfunction "1_1") (pintype "passive"))
      (node (ref "U27") (pin "7") (pinfunction "OUTB_7") (pintype "output"))
    )
    (net (code "45") (name "Net-(X5-OUTPUT)") (class "Default")
      (node (ref "R158") (pin "2") (pinfunction "2_2") (pintype "passive"))
      (node (ref "X5") (pin "3") (pinfunction "OUTPUT_3") (pintype "output"))
    )
    (net (code "46") (name "unconnected-(U23-MSBOUT-Pad8)") (class "Default")
      (node (ref "U23") (pin "8") (pinfunction "MSBOUT_8") (pintype "output"))
    )
    (net (code "47") (name "unconnected-(U23-SYNCOUT-Pad7)") (class "Default")
      (node (ref "U23") (pin "7") (pinfunction "SYNCOUT_7") (pintype "output"))
    )
    (net (code "48") (name "unconnected-(U24B-NC-Pad1)") (class "Default")
      (node (ref "U24") (pin "1") (pinfunction "NC_1") (pintype "passive"))
    )
    (net (code "49") (name "unconnected-(U24B-NC-Pad5)") (class "Default")
      (node (ref "U24") (pin "5") (pinfunction "NC_5") (pintype "passive"))
    )
  )
)
